# LiPo_Battery_Charger.net
KiCad netlist of a schematic drawn in Altium Designer
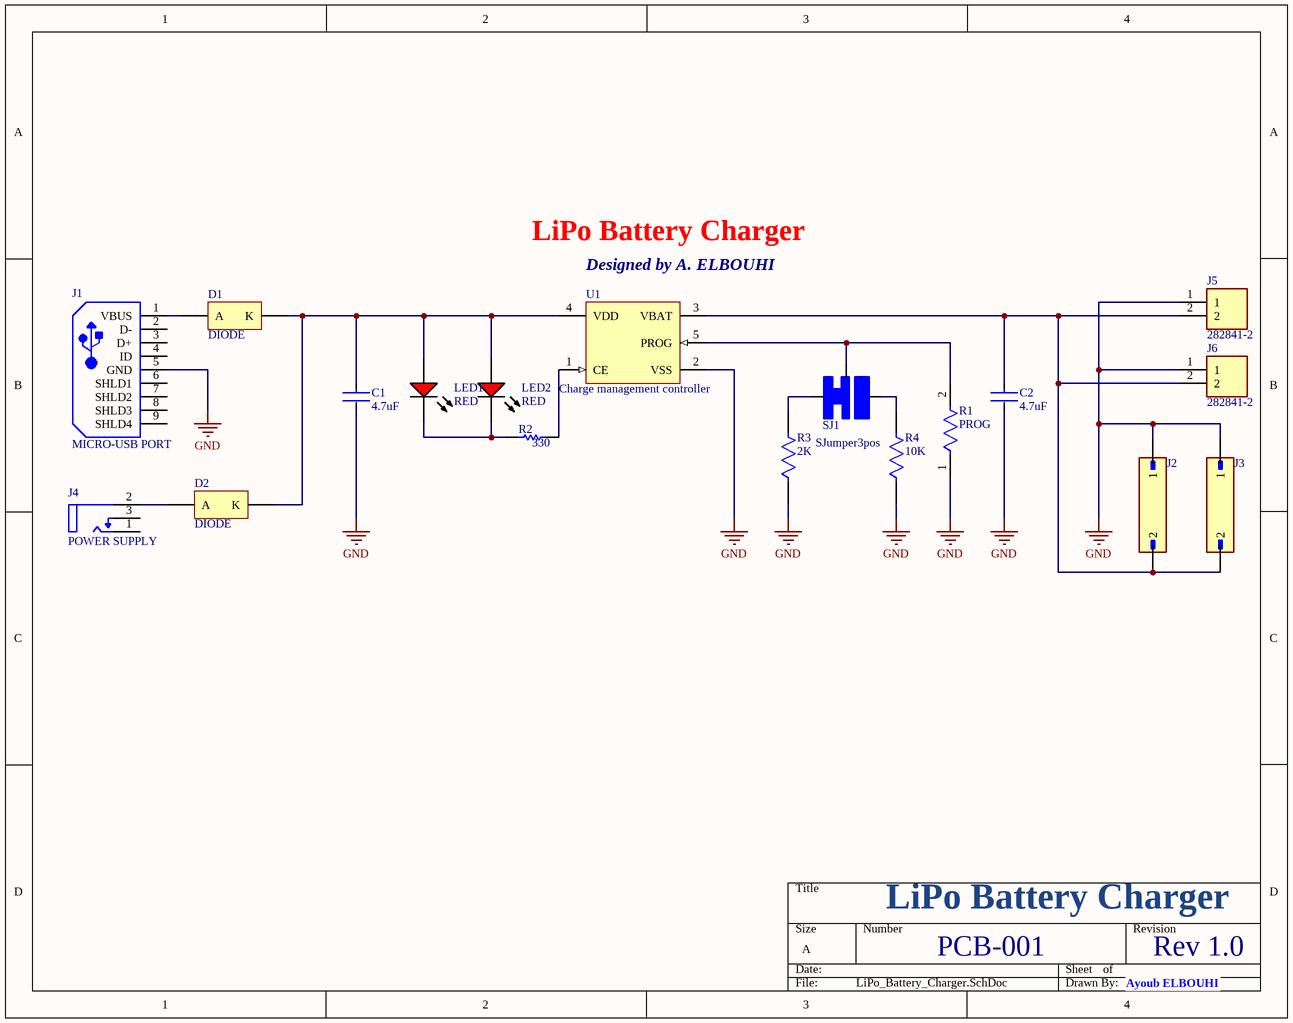
[diagram p0: LiPo_Battery_Charger.SchDoc]

(export (version "E")
  (design (tool "Eeschema 10.0.6"))
  (components
    (comp (ref "C1")
      (value "4.7uF")
      (footprint "FP-GRM155-0_15-IPC_C")
      (description "Chip Multilayer Ceramic Capacitors for General Purpose, 0402, 4.7uF, X6S, 22%, 20%, 6.3V")
      (fields (field (name "TOLERANCE") "20%"))
      (libsource (lib "Altium Content Vault") (part "b4654b650e69147ec39a6b967a45e02"))
    )
    (comp (ref "C2")
      (value "4.7uF")
      (footprint "FP-GRM155-0_15-IPC_C")
      (description "Chip Multilayer Ceramic Capacitors for General Purpose, 0402, 4.7uF, X6S, 22%, 20%, 6.3V")
      (fields (field (name "TOLERANCE") "20%"))
      (libsource (lib "Altium Content Vault") (part "b4654b650e69147ec39a6b967a45e02"))
    )
    (comp (ref "D1")
      (value "DIODE")
      (footprint "ONSC-SMA-2-403D-02_V")
      (description "Schottky Power Rectifier, 2-Pin SMA, Pb-Free, Tape and Reel")
      (fields (field (name "PARTNUMBER") "MBRA140T3G") (field (name "MANUFACTURER") "On Semiconductor"))
      (libsource (lib "Altium Content Vault") (part "ONSC-D-K1A2-2_A"))
    )
    (comp (ref "D2")
      (value "DIODE")
      (footprint "ONSC-SMA-2-403D-02_V")
      (description "Schottky Power Rectifier, 2-Pin SMA, Pb-Free, Tape and Reel")
      (fields (field (name "PARTNUMBER") "MBRA140T3G") (field (name "MANUFACTURER") "On Semiconductor"))
      (libsource (lib "Altium Content Vault") (part "ONSC-D-K1A2-2_A"))
    )
    (comp (ref "J1")
      (value "MICRO-USB PORT")
      (footprint "FCI-10104110-0001LF_V")
      (description "Micro USB, Receptacle, -55 to 85 degC, 5-Pin SMD, RoHS, Tape and Reel")
      (fields (field (name "MANUFACTURER") "FCI Electronics"))
      (libsource (lib "Altium Content Vault") (part "USB-5-4SHLD"))
    )
    (comp (ref "J2")
      (value "67997-402HLF")
      (footprint "AMPHENOL_67997-402HLF")
      (fields (field (name "MF") "{'manufacturer': u'Amphenol ICC (FCI)'}"))
      (libsource (lib "67997-402HLF") (part "67997-402HLF"))
    )
    (comp (ref "J3")
      (value "67997-402HLF")
      (footprint "AMPHENOL_67997-402HLF")
      (fields (field (name "MF") "{'manufacturer': u'Amphenol ICC (FCI)'}"))
      (libsource (lib "67997-402HLF") (part "67997-402HLF"))
    )
    (comp (ref "J4")
      (value "POWER SUPPLY")
      (footprint "FP-RASM722PTR13X-MFG")
      (description "CONN PWR JACK 2.1X5.5MM SOLDER")
      (libsource (lib "Altium Content Vault") (part "69023cd999ddc70d2a190894d9bbb58"))
    )
    (comp (ref "J5")
      (value "282841-2")
      (footprint "TE_282841-2")
      (description "Conn Terminal Block 2 POS 5.08mm Solder ST Thru-Hole 17.5A/Contact")
      (fields (field (name "MF") "TE Connectivity"))
      (libsource (lib "282841-2") (part "282841-2"))
    )
    (comp (ref "J6")
      (value "282841-2")
      (footprint "TE_282841-2")
      (description "Conn Terminal Block 2 POS 5.08mm Solder ST Thru-Hole 17.5A/Contact")
      (fields (field (name "MF") "TE Connectivity"))
      (libsource (lib "282841-2") (part "282841-2"))
    )
    (comp (ref "LED1")
      (value "RED")
      (footprint "INDPR60-254-520X380X650")
      (description "Radial LED, 12.6 mcd, 20 mA, 2 V, -55 to 100 degC, 2-Pin THD, RoHS, Bulk")
      (fields (field (name "TOLERANCE") "20%"))
      (libsource (lib "Altium Content Vault") (part "LED-RED-AK-2"))
    )
    (comp (ref "LED2")
      (value "RED")
      (footprint "INDPR60-254-520X380X650")
      (description "Radial LED, 12.6 mcd, 20 mA, 2 V, -55 to 100 degC, 2-Pin THD, RoHS, Bulk")
      (fields (field (name "TOLERANCE") "20%"))
      (libsource (lib "Altium Content Vault") (part "LED-RED-AK-2"))
    )
    (comp (ref "R1")
      (value "PROG")
      (footprint "FP-CF18-MFG")
      (description "RES 10K OHM 1/8W 5% CF AXIAL")
      (fields
        (field (name "MANUFACTURER PART NUMBER") "CF18JT10K0")
        (field (name "MANUFACTURER") "Stackpole Electronics")
      )
      (libsource (lib "Altium Content Vault") (part "1029c3af85768c4190bb7ad29bc67b5"))
    )
    (comp (ref "R2")
      (value "330")
      (footprint "RESC3225X60X45ML20T20")
      (fields (field (name "PART NUMBER") "CRCW1210330RJNTA") (field (name "MANUFACTURER") "Vishay Dale"))
      (libsource (lib "Altium Content Vault") (part "RES"))
    )
    (comp (ref "R3")
      (value "2K")
      (footprint "FP-CR0603-IPC_B")
      (description "Thick Film Chip Resistors 0603 2kΩ 0.1W 5% 200ppm/°C")
      (fields (field (name "TOLERANCE") "5%"))
      (libsource (lib "") (part "1029c3af85768c4190bb7ad29bc67b5_1"))
    )
    (comp (ref "R4")
      (value "10K")
      (footprint "FP-TFCR0805-IPC_B")
      (description "RES Thin Film,  10kΩ, 0.1%, 0.1W, 50ppm/°C, 0805")
      (libsource (lib "") (part "1029c3af85768c4190bb7ad29bc67b5_1"))
    )
    (comp (ref "SJ1")
      (value "SJumper3pos")
      (footprint "PCBComponent_1")
      (description "solder jumper 3 pins")
      (libsource (lib "solder_jumper_3posSchLib") (part "Solder_jumper_3pos"))
    )
    (comp (ref "U1")
      (value "Charge management controller")
      (footprint "SOT-23-OT5_M")
      (libsource (lib "Altium Content Vault") (part "PM-BM-MCP7381X-SOT5"))
    )
  )
  (nets
    (net (code "1") (name "GND") (class "Default")
      (node (ref "C1") (pin "2") (pinfunction "2_2") (pintype "passive"))
      (node (ref "C2") (pin "2") (pinfunction "2_2") (pintype "passive"))
      (node (ref "J1") (pin "5") (pinfunction "GND_5") (pintype "power_in"))
      (node (ref "J2") (pin "1") (pinfunction "1_1") (pintype "passive"))
      (node (ref "J3") (pin "1") (pinfunction "1_1") (pintype "passive"))
      (node (ref "J5") (pin "1") (pinfunction "1_1") (pintype "passive"))
      (node (ref "J6") (pin "1") (pinfunction "1_1") (pintype "passive"))
      (node (ref "R1") (pin "1") (pinfunction "1_1") (pintype "passive"))
      (node (ref "R3") (pin "1") (pinfunction "1_1") (pintype "passive"))
      (node (ref "R4") (pin "1") (pinfunction "1_1") (pintype "passive"))
      (node (ref "U1") (pin "2") (pinfunction "VSS_2") (pintype "power_in"))
    )
    (net (code "2") (name "Net-(D1-A)") (class "Default")
      (node (ref "D1") (pin "2") (pinfunction "A_2") (pintype "passive"))
      (node (ref "J1") (pin "1") (pinfunction "VBUS_1") (pintype "power_in"))
    )
    (net (code "3") (name "Net-(D1-K)") (class "Default")
      (node (ref "C1") (pin "1") (pinfunction "1_1") (pintype "passive"))
      (node (ref "D1") (pin "1") (pinfunction "K_1") (pintype "passive"))
      (node (ref "D2") (pin "1") (pinfunction "K_1") (pintype "passive"))
      (node (ref "LED1") (pin "1") (pinfunction "A_1") (pintype "passive"))
      (node (ref "LED2") (pin "1") (pinfunction "A_1") (pintype "passive"))
      (node (ref "U1") (pin "4") (pinfunction "VDD_4") (pintype "power_in"))
    )
    (net (code "4") (name "Net-(D2-A)") (class "Default")
      (node (ref "D2") (pin "2") (pinfunction "A_2") (pintype "passive"))
      (node (ref "J4") (pin "2") (pinfunction "SLEEVE_TERMINAL_2") (pintype "passive"))
    )
    (net (code "5") (name "Net-(LED1-K)") (class "Default")
      (node (ref "LED1") (pin "2") (pinfunction "K_2") (pintype "passive"))
      (node (ref "LED2") (pin "2") (pinfunction "K_2") (pintype "passive"))
      (node (ref "R2") (pin "1") (pinfunction "1_1") (pintype "passive"))
    )
    (net (code "6") (name "Net-(R3-Pad2)") (class "Default")
      (node (ref "R3") (pin "2") (pinfunction "2_2") (pintype "passive"))
      (node (ref "SJ1") (pin "1") (pinfunction "1_1") (pintype "passive"))
    )
    (net (code "7") (name "Net-(R4-Pad2)") (class "Default")
      (node (ref "R4") (pin "2") (pinfunction "2_2") (pintype "passive"))
      (node (ref "SJ1") (pin "3") (pinfunction "3_3") (pintype "passive"))
    )
    (net (code "8") (name "Net-(U1-CE)") (class "Default")
      (node (ref "R2") (pin "2") (pinfunction "2_2") (pintype "passive"))
      (node (ref "U1") (pin "1") (pinfunction "CE_1") (pintype "input"))
    )
    (net (code "9") (name "Net-(U1-PROG)") (class "Default")
      (node (ref "R1") (pin "2") (pinfunction "2_2") (pintype "passive"))
      (node (ref "SJ1") (pin "2") (pinfunction "2_2") (pintype "passive"))
      (node (ref "U1") (pin "5") (pinfunction "PROG_5") (pintype "input"))
    )
    (net (code "10") (name "Net-(U1-VBAT)") (class "Default")
      (node (ref "C2") (pin "1") (pinfunction "1_1") (pintype "passive"))
      (node (ref "J2") (pin "2") (pinfunction "2_2") (pintype "passive"))
      (node (ref "J3") (pin "2") (pinfunction "2_2") (pintype "passive"))
      (node (ref "J5") (pin "2") (pinfunction "2_2") (pintype "passive"))
      (node (ref "J6") (pin "2") (pinfunction "2_2") (pintype "passive"))
      (node (ref "U1") (pin "3") (pinfunction "VBAT_3") (pintype "power_in"))
    )
    (net (code "11") (name "unconnected-(J1-D+-Pad3)") (class "Default")
      (node (ref "J1") (pin "3") (pinfunction "D+_3") (pintype "passive"))
    )
    (net (code "12") (name "unconnected-(J1-D--Pad2)") (class "Default")
      (node (ref "J1") (pin "2") (pinfunction "D-_2") (pintype "passive"))
    )
    (net (code "13") (name "unconnected-(J1-ID-Pad4)") (class "Default")
      (node (ref "J1") (pin "4") (pinfunction "ID_4") (pintype "passive"))
    )
    (net (code "14") (name "unconnected-(J1-SHLD1-Pad6)") (class "Default")
      (node (ref "J1") (pin "6") (pinfunction "SHLD1_6") (pintype "passive"))
    )
    (net (code "15") (name "unconnected-(J1-SHLD2-Pad7)") (class "Default")
      (node (ref "J1") (pin "7") (pinfunction "SHLD2_7") (pintype "passive"))
    )
    (net (code "16") (name "unconnected-(J1-SHLD3-Pad8)") (class "Default")
      (node (ref "J1") (pin "8") (pinfunction "SHLD3_8") (pintype "passive"))
    )
    (net (code "17") (name "unconnected-(J1-SHLD4-Pad9)") (class "Default")
      (node (ref "J1") (pin "9") (pinfunction "SHLD4_9") (pintype "passive"))
    )
    (net (code "18") (name "unconnected-(J4-SHUNT_TERMINAL-Pad3)") (class "Default")
      (node (ref "J4") (pin "3") (pinfunction "SHUNT_TERMINAL_3") (pintype "passive"))
    )
    (net (code "19") (name "unconnected-(J4-TIP_TERMINAL(CENTER_PIN)-Pad1)") (class "Default")
      (node (ref "J4") (pin "1") (pinfunction "TIP_TERMINAL(CENTER_PIN)_1") (pintype "passive"))
    )
  )
)
